# DrizzlingBytes.net
KiCad netlist of a schematic drawn in EAGLE
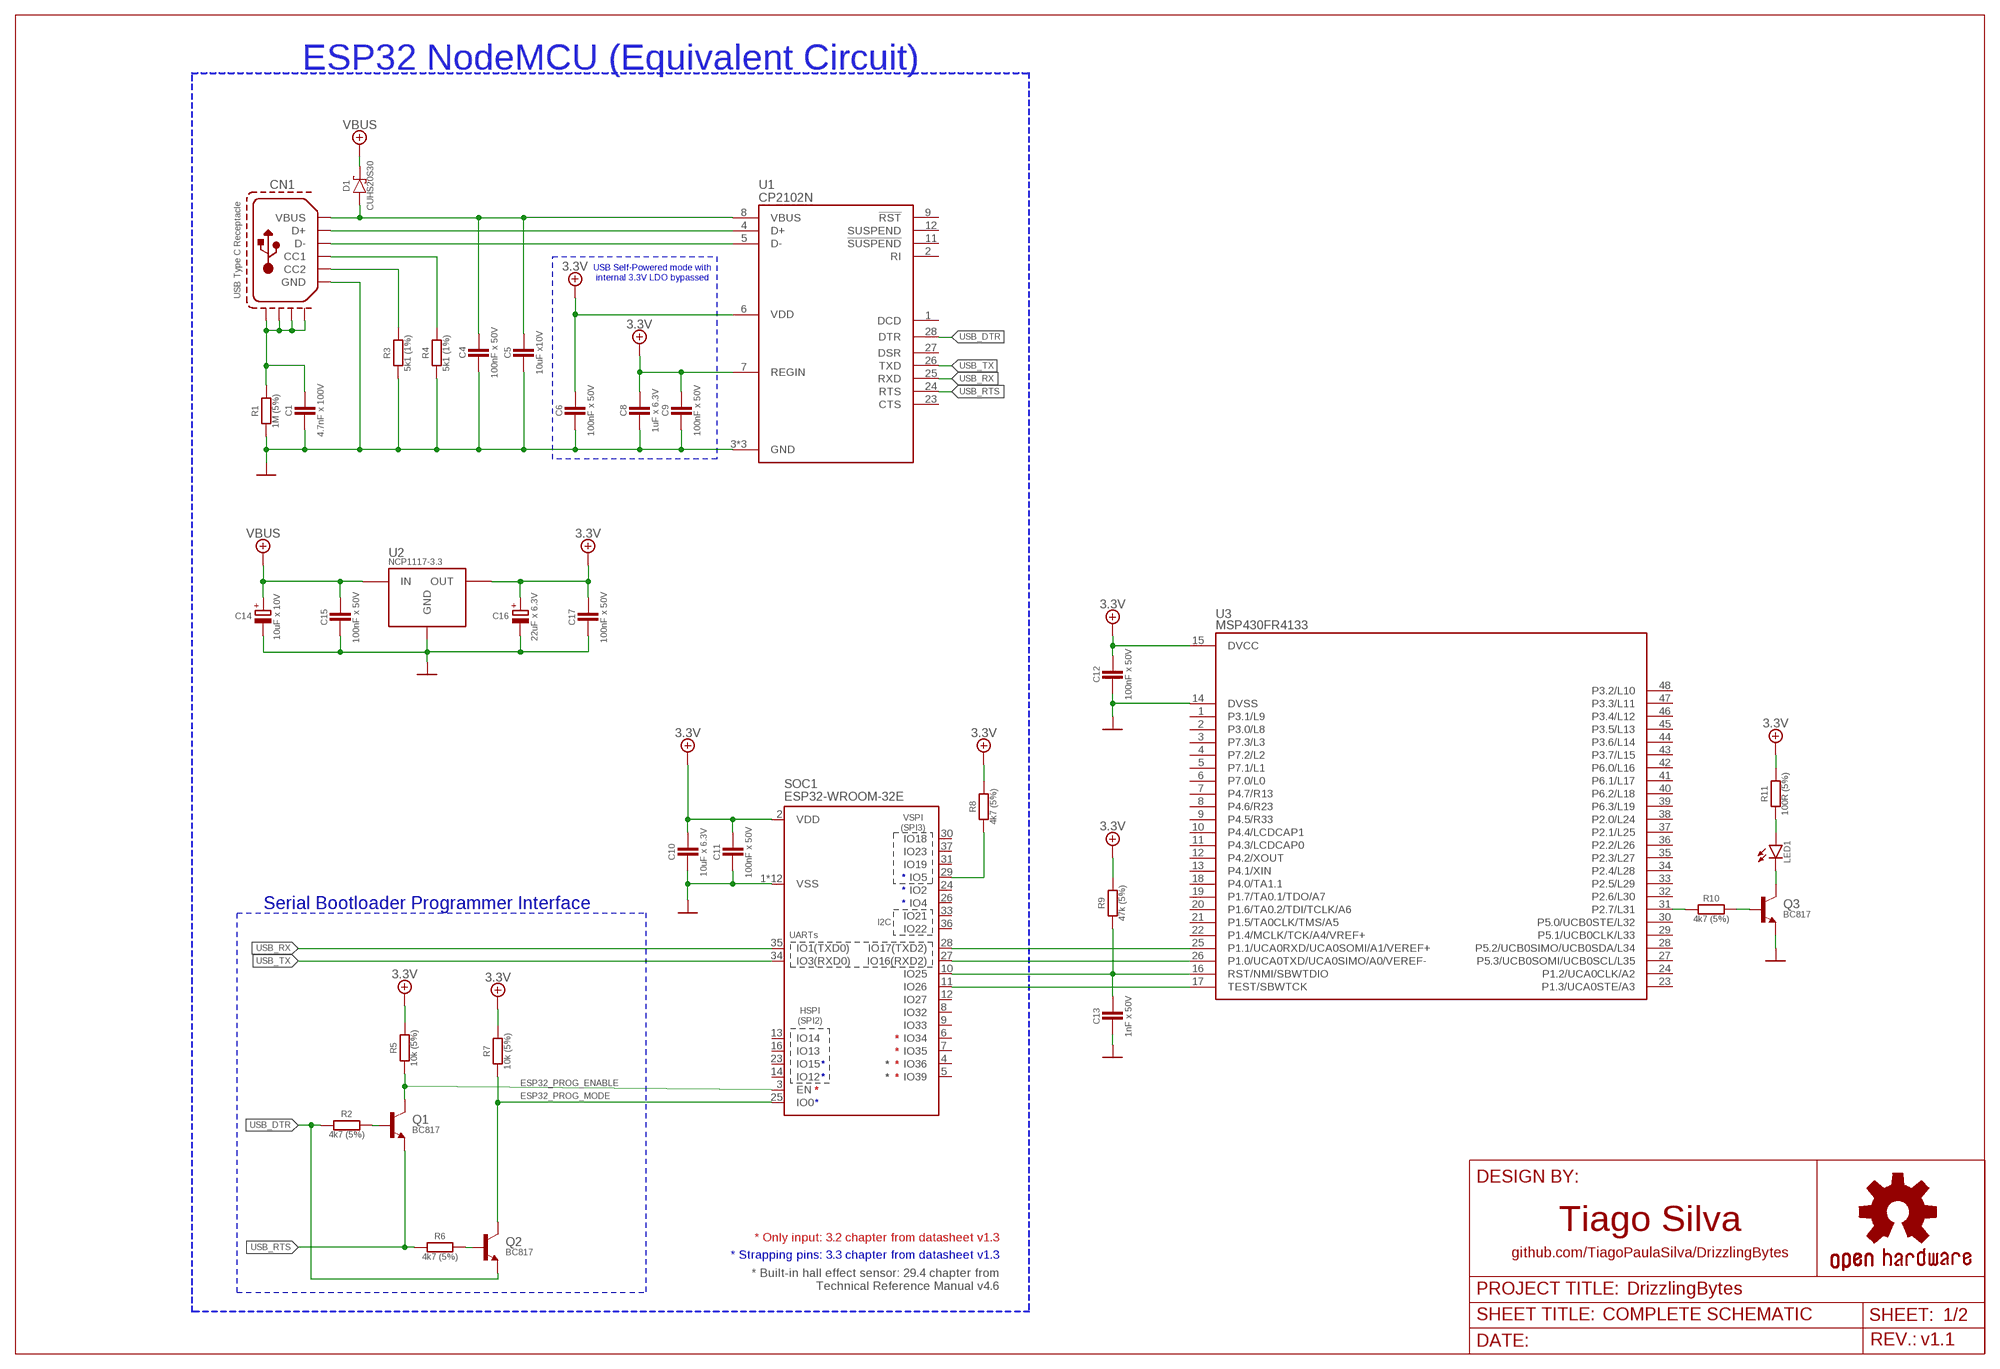
[diagram p0: schematic, sheet 1]
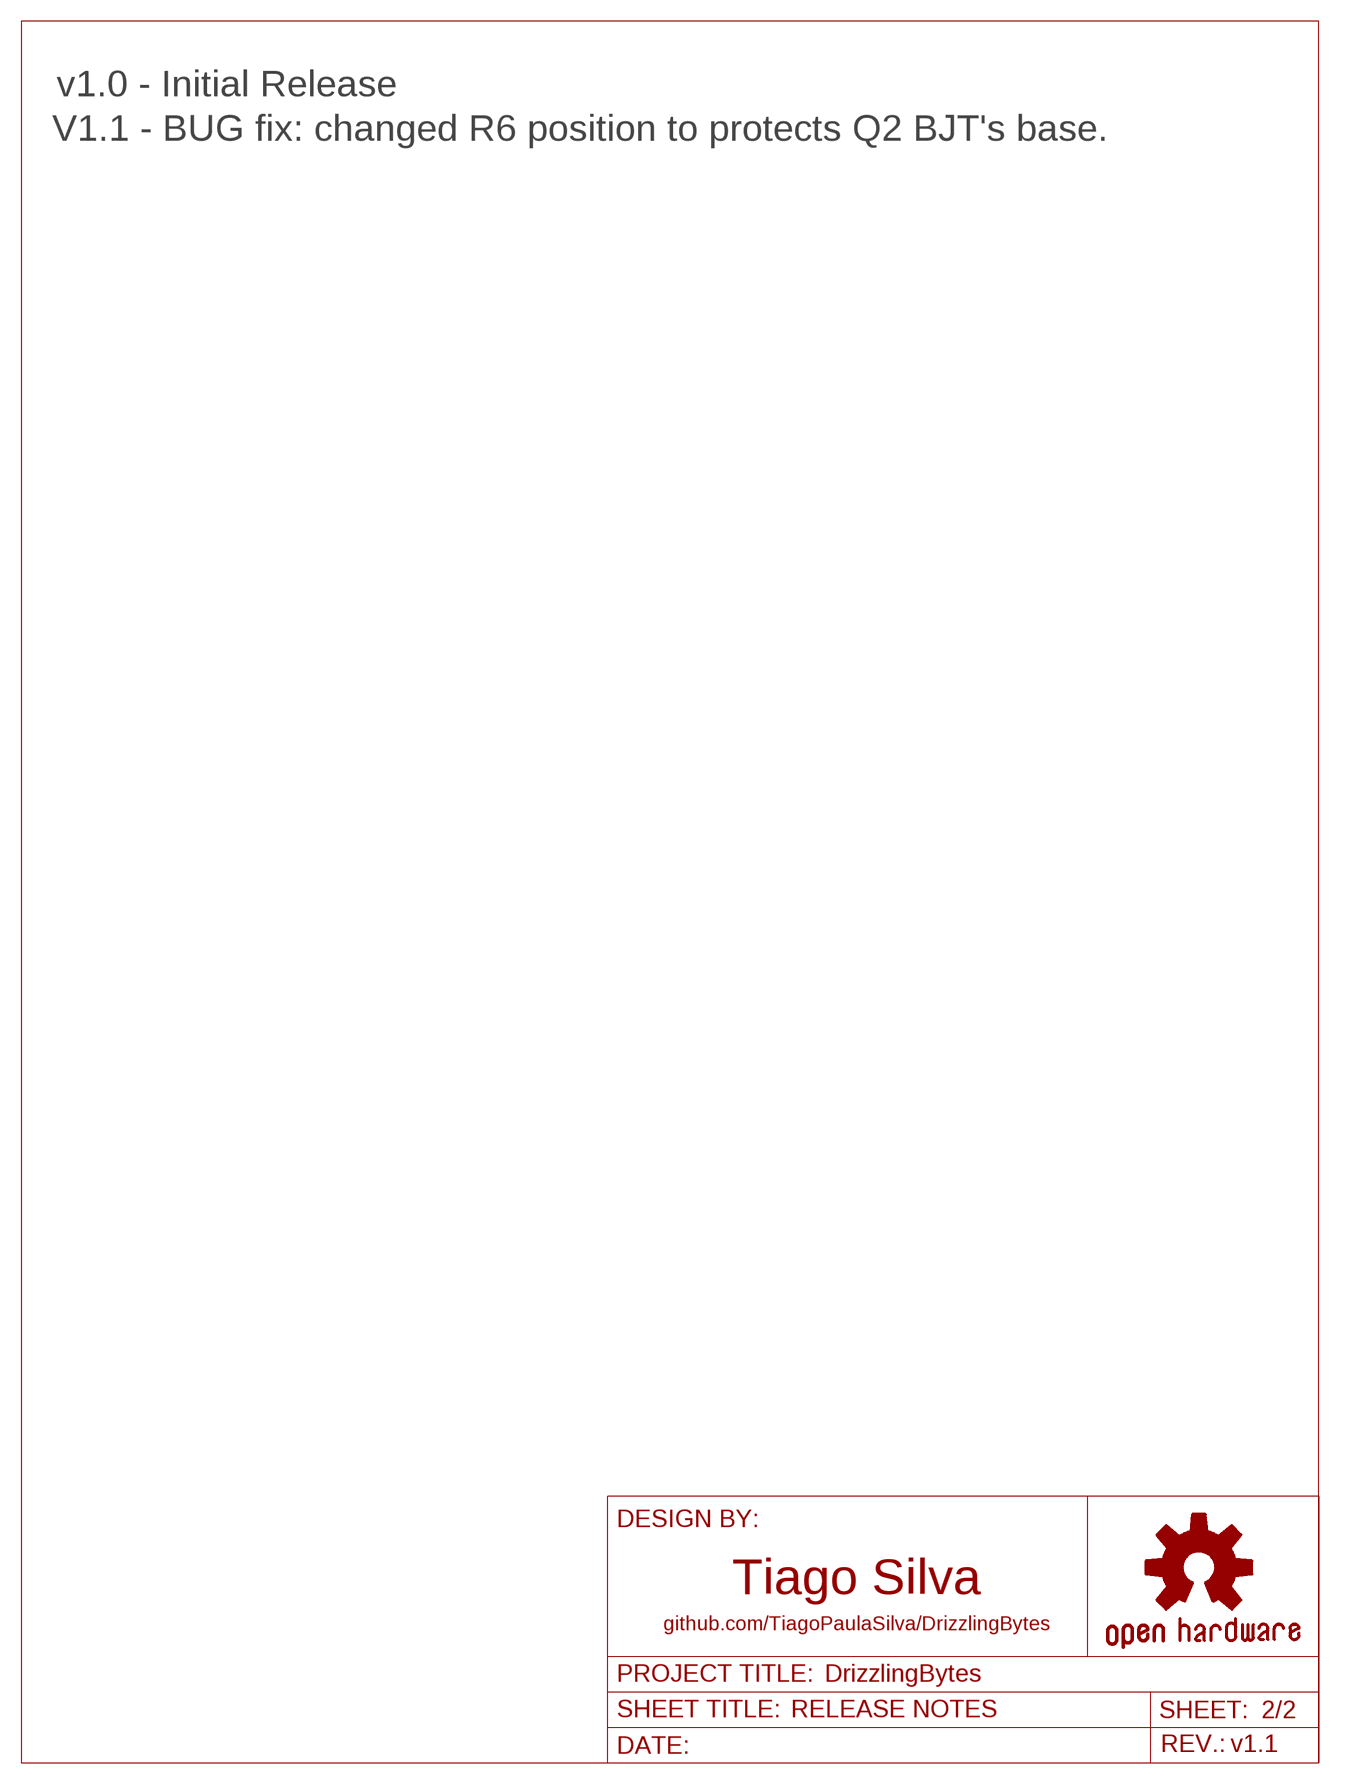
[diagram p1: schematic, sheet 2]

(export (version "E")
  (design (tool "Eeschema 10.0.6"))
  (components
    (comp (ref "C1")
      (value "4.7nF x 100V")
      (footprint "eagle-import:C0402")
      (libsource (lib "eagle-import") (part "C_0402"))
    )
    (comp (ref "C4")
      (value "100nF x 50V")
      (footprint "eagle-import:C0402")
      (libsource (lib "eagle-import") (part "C_0402"))
    )
    (comp (ref "C5")
      (value "10uF x10V")
      (footprint "eagle-import:C0402")
      (libsource (lib "eagle-import") (part "C_0402"))
    )
    (comp (ref "C6")
      (value "100nF x 50V")
      (footprint "eagle-import:C0402")
      (libsource (lib "eagle-import") (part "C_0402"))
    )
    (comp (ref "C8")
      (value "1uF x 6.3V")
      (footprint "eagle-import:C0402")
      (libsource (lib "eagle-import") (part "C_0402"))
    )
    (comp (ref "C9")
      (value "100nF x 50V")
      (footprint "eagle-import:C0402")
      (libsource (lib "eagle-import") (part "C_0402"))
    )
    (comp (ref "C10")
      (value "10uF x 6.3V")
      (footprint "eagle-import:C0402")
      (libsource (lib "eagle-import") (part "C_0402"))
    )
    (comp (ref "C11")
      (value "100nF x 50V")
      (footprint "eagle-import:C0402")
      (libsource (lib "eagle-import") (part "C_0402"))
    )
    (comp (ref "C12")
      (value "100nF x 50V")
      (footprint "eagle-import:C0402")
      (libsource (lib "eagle-import") (part "C_0402"))
    )
    (comp (ref "C13")
      (value "1nF x 50V")
      (footprint "eagle-import:C0402")
      (libsource (lib "eagle-import") (part "C_0402"))
    )
    (comp (ref "C14")
      (value "10uF x 10V")
      (footprint "eagle-import:C1206_POL")
      (description "Tantalum Electrolytic Capacitors (Low ESR)")
      (libsource (lib "eagle-import") (part "CP_1206_POL"))
    )
    (comp (ref "C15")
      (value "100nF x 50V")
      (footprint "eagle-import:C0402")
      (libsource (lib "eagle-import") (part "C_0402"))
    )
    (comp (ref "C16")
      (value "22uF x 6.3V")
      (footprint "eagle-import:C1206_POL")
      (description "Tantalum Electrolytic Capacitors (Low ESR)")
      (libsource (lib "eagle-import") (part "CP_1206_POL"))
    )
    (comp (ref "C17")
      (value "100nF x 50V")
      (footprint "eagle-import:C0402")
      (libsource (lib "eagle-import") (part "C_0402"))
    )
    (comp (ref "CN1")
      (value "USB Type C Receptacle")
      (footprint "eagle-import:USB-C-16P-2LAYER-PADS")
      (libsource (lib "eagle-import") (part "USB-C-16P-2LAYERS"))
    )
    (comp (ref "D1")
      (value "SCHOTTKY-CUHS20S30")
      (footprint "eagle-import:US2H-2")
      (fields (field (name "FAMILY") "CUHS20S30"))
      (libsource (lib "eagle-import") (part "SCHOTTKY-CUHS20S30"))
    )
    (comp (ref "LED1")
      (value "LED-0402")
      (footprint "eagle-import:LED-0402")
      (libsource (lib "eagle-import") (part "LED-0402"))
    )
    (comp (ref "Q1")
      (value "NPN-BC817")
      (footprint "eagle-import:SOT23-3")
      (fields (field (name "FAMILY") "BC817"))
      (libsource (lib "eagle-import") (part "NPN-BC817"))
    )
    (comp (ref "Q2")
      (value "NPN-BC817")
      (footprint "eagle-import:SOT23-3")
      (fields (field (name "FAMILY") "BC817"))
      (libsource (lib "eagle-import") (part "NPN-BC817"))
    )
    (comp (ref "Q3")
      (value "NPN-BC817")
      (footprint "eagle-import:SOT23-3")
      (fields (field (name "FAMILY") "BC817"))
      (libsource (lib "eagle-import") (part "NPN-BC817"))
    )
    (comp (ref "R1")
      (value "1M (5%)")
      (footprint "eagle-import:R0402")
      (libsource (lib "eagle-import") (part "R_0402"))
    )
    (comp (ref "R2")
      (value "4k7 (5%)")
      (footprint "eagle-import:R0402")
      (libsource (lib "eagle-import") (part "R_0402"))
    )
    (comp (ref "R3")
      (value "5k1 (1%)")
      (footprint "eagle-import:R0402")
      (libsource (lib "eagle-import") (part "R_0402"))
    )
    (comp (ref "R4")
      (value "5k1 (1%)")
      (footprint "eagle-import:R0402")
      (libsource (lib "eagle-import") (part "R_0402"))
    )
    (comp (ref "R5")
      (value "10k (5%)")
      (footprint "eagle-import:R0402")
      (libsource (lib "eagle-import") (part "R_0402"))
    )
    (comp (ref "R6")
      (value "4k7 (5%)")
      (footprint "eagle-import:R0402")
      (libsource (lib "eagle-import") (part "R_0402"))
    )
    (comp (ref "R7")
      (value "10k (5%)")
      (footprint "eagle-import:R0402")
      (libsource (lib "eagle-import") (part "R_0402"))
    )
    (comp (ref "R8")
      (value "4k7 (5%)")
      (footprint "eagle-import:R0402")
      (libsource (lib "eagle-import") (part "R_0402"))
    )
    (comp (ref "R9")
      (value "47k (5%)")
      (footprint "eagle-import:R0402")
      (libsource (lib "eagle-import") (part "R_0402"))
    )
    (comp (ref "R10")
      (value "4k7 (5%)")
      (footprint "eagle-import:R0402")
      (libsource (lib "eagle-import") (part "R_0402"))
    )
    (comp (ref "R11")
      (value "100R (5%)")
      (footprint "eagle-import:R0402")
      (libsource (lib "eagle-import") (part "R_0402"))
    )
    (comp (ref "SOC1")
      (value "ESP32-WROOM-32E")
      (footprint "eagle-import:ESP32-WROOM-32E")
      (libsource (lib "eagle-import") (part "ESP32-WROOM-32E-N4"))
    )
    (comp (ref "U1")
      (value "CP2102N")
      (footprint "eagle-import:QFN-28")
      (libsource (lib "eagle-import") (part "CP2102N"))
    )
    (comp (ref "U2")
      (value "1117-3.3V")
      (footprint "eagle-import:SOT-223-3")
      (fields (field (name "FAMILY") "LT1117-3.3") (field (name "FAMILY_1") "NCP1117-3.3"))
      (libsource (lib "eagle-import") (part "1117-3.3V"))
    )
    (comp (ref "U3")
      (value "MSP430FR4133")
      (footprint "eagle-import:TSSOP-48")
      (fields
        (field (name "MANUFACTURER_PART_NUMBER") "MSP430FR4133IG48R")
        (field (name "MOUSER_PART_NUMBER") "595-MSP430R4133IG48R")
      )
      (libsource (lib "eagle-import") (part "MSP430FR4133IG48R"))
    )
  )
  (nets
    (net (code "1") (name "0V") (class "Default")
      (node (ref "C1") (pin "1") (pinfunction "1_1") (pintype "passive"))
      (node (ref "C10") (pin "2") (pinfunction "2_2") (pintype "passive"))
      (node (ref "C11") (pin "2") (pinfunction "2_2") (pintype "passive"))
      (node (ref "C12") (pin "1") (pinfunction "1_1") (pintype "passive"))
      (node (ref "C13") (pin "2") (pinfunction "2_2") (pintype "passive"))
      (node (ref "C14") (pin "2") (pinfunction "-_2") (pintype "passive"))
      (node (ref "C15") (pin "2") (pinfunction "2_2") (pintype "passive"))
      (node (ref "C16") (pin "2") (pinfunction "-_2") (pintype "passive"))
      (node (ref "C17") (pin "2") (pinfunction "2_2") (pintype "passive"))
      (node (ref "C4") (pin "1") (pinfunction "1_1") (pintype "passive"))
      (node (ref "C5") (pin "1") (pinfunction "1_1") (pintype "passive"))
      (node (ref "C6") (pin "1") (pinfunction "1_1") (pintype "passive"))
      (node (ref "C8") (pin "1") (pinfunction "1_1") (pintype "passive"))
      (node (ref "C9") (pin "1") (pinfunction "1_1") (pintype "passive"))
      (node (ref "CN1") (pin "GND") (pinfunction "GND_GND") (pintype "bidirectional"))
      (node (ref "CN1") (pin "GND2") (pinfunction "GND_GND2") (pintype "bidirectional"))
      (node (ref "Q3") (pin "2") (pinfunction "E_2") (pintype "passive"))
      (node (ref "R1") (pin "2") (pinfunction "2_2") (pintype "passive"))
      (node (ref "R3") (pin "2") (pinfunction "2_2") (pintype "passive"))
      (node (ref "R4") (pin "2") (pinfunction "2_2") (pintype "passive"))
      (node (ref "SOC1") (pin "1") (pinfunction "VSS_1") (pintype "power_in"))
      (node (ref "SOC1") (pin "15") (pinfunction "VSS_15") (pintype "power_in"))
      (node (ref "SOC1") (pin "38") (pinfunction "VSS_38") (pintype "power_in"))
      (node (ref "SOC1") (pin "E1") (pinfunction "VSS_E1") (pintype "power_in"))
      (node (ref "SOC1") (pin "E2") (pinfunction "VSS_E2") (pintype "power_in"))
      (node (ref "SOC1") (pin "E3") (pinfunction "VSS_E3") (pintype "power_in"))
      (node (ref "SOC1") (pin "E4") (pinfunction "VSS_E4") (pintype "power_in"))
      (node (ref "SOC1") (pin "E5") (pinfunction "VSS_E5") (pintype "power_in"))
      (node (ref "SOC1") (pin "E6") (pinfunction "VSS_E6") (pintype "power_in"))
      (node (ref "SOC1") (pin "E7") (pinfunction "VSS_E7") (pintype "power_in"))
      (node (ref "SOC1") (pin "E8") (pinfunction "VSS_E8") (pintype "power_in"))
      (node (ref "SOC1") (pin "E9") (pinfunction "VSS_E9") (pintype "power_in"))
      (node (ref "U1") (pin "3") (pinfunction "GND_3") (pintype "power_in"))
      (node (ref "U1") (pin "EXP") (pinfunction "GND_EXP") (pintype "power_in"))
      (node (ref "U1") (pin "M") (pinfunction "GND_M") (pintype "power_in"))
      (node (ref "U2") (pin "1") (pinfunction "GND_1") (pintype "bidirectional"))
      (node (ref "U3") (pin "14") (pinfunction "DVSS_14") (pintype "bidirectional"))
    )
    (net (code "2") (name "3.3V") (class "Default")
      (node (ref "C10") (pin "1") (pinfunction "1_1") (pintype "passive"))
      (node (ref "C11") (pin "1") (pinfunction "1_1") (pintype "passive"))
      (node (ref "C12") (pin "2") (pinfunction "2_2") (pintype "passive"))
      (node (ref "C16") (pin "1") (pinfunction "+_1") (pintype "passive"))
      (node (ref "C17") (pin "1") (pinfunction "1_1") (pintype "passive"))
      (node (ref "C6") (pin "2") (pinfunction "2_2") (pintype "passive"))
      (node (ref "C8") (pin "2") (pinfunction "2_2") (pintype "passive"))
      (node (ref "C9") (pin "2") (pinfunction "2_2") (pintype "passive"))
      (node (ref "R11") (pin "2") (pinfunction "2_2") (pintype "passive"))
      (node (ref "R5") (pin "1") (pinfunction "1_1") (pintype "passive"))
      (node (ref "R7") (pin "1") (pinfunction "1_1") (pintype "passive"))
      (node (ref "R8") (pin "2") (pinfunction "2_2") (pintype "passive"))
      (node (ref "R9") (pin "2") (pinfunction "2_2") (pintype "passive"))
      (node (ref "SOC1") (pin "2") (pinfunction "VDD_2") (pintype "power_in"))
      (node (ref "U1") (pin "6") (pinfunction "VDD_6") (pintype "power_in"))
      (node (ref "U1") (pin "7") (pinfunction "REGIN_7") (pintype "passive"))
      (node (ref "U2") (pin "2") (pinfunction "OUT_2") (pintype "bidirectional"))
      (node (ref "U2") (pin "4") (pinfunction "OUT_4") (pintype "bidirectional"))
      (node (ref "U3") (pin "15") (pinfunction "DVCC_15") (pintype "bidirectional"))
    )
    (net (code "3") (name "ESP32_PROG_ENABLE") (class "Default")
      (node (ref "Q1") (pin "3") (pinfunction "C_3") (pintype "passive"))
      (node (ref "R5") (pin "2") (pinfunction "2_2") (pintype "passive"))
      (node (ref "SOC1") (pin "3") (pinfunction "EN_3") (pintype "input"))
    )
    (net (code "4") (name "ESP32_PROG_MODE") (class "Default")
      (node (ref "Q2") (pin "3") (pinfunction "C_3") (pintype "passive"))
      (node (ref "R7") (pin "2") (pinfunction "2_2") (pintype "passive"))
      (node (ref "SOC1") (pin "25") (pinfunction "IO0_25") (pintype "bidirectional"))
    )
    (net (code "5") (name "Net-(CN1-CC1)") (class "Default")
      (node (ref "CN1") (pin "A5") (pinfunction "CC1_A5") (pintype "bidirectional"))
      (node (ref "R4") (pin "1") (pinfunction "1_1") (pintype "passive"))
    )
    (net (code "6") (name "Net-(CN1-CC2)") (class "Default")
      (node (ref "CN1") (pin "B5") (pinfunction "CC2_B5") (pintype "bidirectional"))
      (node (ref "R3") (pin "1") (pinfunction "1_1") (pintype "passive"))
    )
    (net (code "7") (name "Net-(CN1-S1)") (class "Default")
      (node (ref "C1") (pin "2") (pinfunction "2_2") (pintype "passive"))
      (node (ref "CN1") (pin "SHLD1") (pinfunction "S1_SHLD1") (pintype "passive"))
      (node (ref "CN1") (pin "SHLD2") (pinfunction "S2_SHLD2") (pintype "passive"))
      (node (ref "CN1") (pin "SHLD3") (pinfunction "S3_SHLD3") (pintype "passive"))
      (node (ref "CN1") (pin "SHLD4") (pinfunction "S4_SHLD4") (pintype "passive"))
      (node (ref "R1") (pin "1") (pinfunction "1_1") (pintype "passive"))
    )
    (net (code "8") (name "Net-(D1-A)") (class "Default")
      (node (ref "C4") (pin "2") (pinfunction "2_2") (pintype "passive"))
      (node (ref "C5") (pin "2") (pinfunction "2_2") (pintype "passive"))
      (node (ref "CN1") (pin "VBUS1") (pinfunction "VBUS_VBUS1") (pintype "bidirectional"))
      (node (ref "CN1") (pin "VBUS2") (pinfunction "VBUS_VBUS2") (pintype "bidirectional"))
      (node (ref "D1") (pin "2") (pinfunction "A_2") (pintype "passive"))
      (node (ref "U1") (pin "8") (pinfunction "VBUS_8") (pintype "passive"))
    )
    (net (code "9") (name "Net-(LED1-A)") (class "Default")
      (node (ref "LED1") (pin "2") (pinfunction "A_2") (pintype "passive"))
      (node (ref "R11") (pin "1") (pinfunction "1_1") (pintype "passive"))
    )
    (net (code "10") (name "Net-(LED1-K)") (class "Default")
      (node (ref "LED1") (pin "1") (pinfunction "K_1") (pintype "passive"))
      (node (ref "Q3") (pin "3") (pinfunction "C_3") (pintype "passive"))
    )
    (net (code "11") (name "Net-(Q1-B)") (class "Default")
      (node (ref "Q1") (pin "1") (pinfunction "B_1") (pintype "passive"))
      (node (ref "R2") (pin "1") (pinfunction "1_1") (pintype "passive"))
    )
    (net (code "12") (name "Net-(Q2-B)") (class "Default")
      (node (ref "Q2") (pin "1") (pinfunction "B_1") (pintype "passive"))
      (node (ref "R6") (pin "2") (pinfunction "2_2") (pintype "passive"))
    )
    (net (code "13") (name "Net-(Q3-B)") (class "Default")
      (node (ref "Q3") (pin "1") (pinfunction "B_1") (pintype "passive"))
      (node (ref "R10") (pin "2") (pinfunction "2_2") (pintype "passive"))
    )
    (net (code "14") (name "Net-(SOC1-IO5)") (class "Default")
      (node (ref "R8") (pin "1") (pinfunction "1_1") (pintype "passive"))
      (node (ref "SOC1") (pin "29") (pinfunction "IO5_29") (pintype "bidirectional"))
    )
    (net (code "15") (name "Net-(SOC1-IO16(RXD2))") (class "Default")
      (node (ref "SOC1") (pin "27") (pinfunction "IO16(RXD2)_27") (pintype "bidirectional"))
      (node (ref "U3") (pin "26") (pinfunction "P1.0/UCA0TXD/UCA0SIMO/A0/VEREF-_26") (pintype "bidirectional"))
    )
    (net (code "16") (name "Net-(SOC1-IO17(TXD2))") (class "Default")
      (node (ref "SOC1") (pin "28") (pinfunction "IO17(TXD2)_28") (pintype "bidirectional"))
      (node (ref "U3") (pin "25") (pinfunction "P1.1/UCA0RXD/UCA0SOMI/A1/VEREF+_25") (pintype "bidirectional"))
    )
    (net (code "17") (name "Net-(SOC1-IO25)") (class "Default")
      (node (ref "C13") (pin "1") (pinfunction "1_1") (pintype "passive"))
      (node (ref "R9") (pin "1") (pinfunction "1_1") (pintype "passive"))
      (node (ref "SOC1") (pin "10") (pinfunction "IO25_10") (pintype "bidirectional"))
      (node (ref "U3") (pin "16") (pinfunction "RST/NMI/SBWTDIO_16") (pintype "bidirectional"))
    )
    (net (code "18") (name "Net-(SOC1-IO26)") (class "Default")
      (node (ref "SOC1") (pin "11") (pinfunction "IO26_11") (pintype "bidirectional"))
      (node (ref "U3") (pin "17") (pinfunction "TEST/SBWTCK_17") (pintype "bidirectional"))
    )
    (net (code "19") (name "Net-(U1-D+)") (class "Default")
      (node (ref "CN1") (pin "A6") (pinfunction "D+_A6") (pintype "bidirectional"))
      (node (ref "CN1") (pin "B6") (pinfunction "D+_B6") (pintype "bidirectional"))
      (node (ref "U1") (pin "4") (pinfunction "D+_4") (pintype "bidirectional"))
    )
    (net (code "20") (name "Net-(U1-D-)") (class "Default")
      (node (ref "CN1") (pin "A7") (pinfunction "D-_A7") (pintype "bidirectional"))
      (node (ref "CN1") (pin "B7") (pinfunction "D-_B7") (pintype "bidirectional"))
      (node (ref "U1") (pin "5") (pinfunction "D-_5") (pintype "bidirectional"))
    )
    (net (code "21") (name "Net-(U3-P2.7{slash}L31)") (class "Default")
      (node (ref "R10") (pin "1") (pinfunction "1_1") (pintype "passive"))
      (node (ref "U3") (pin "31") (pinfunction "P2.7/L31_31") (pintype "bidirectional"))
    )
    (net (code "22") (name "USB_DTR") (class "Default")
      (node (ref "Q2") (pin "2") (pinfunction "E_2") (pintype "passive"))
      (node (ref "R2") (pin "2") (pinfunction "2_2") (pintype "passive"))
      (node (ref "U1") (pin "28") (pinfunction "DTR_28") (pintype "output"))
    )
    (net (code "23") (name "USB_RTS") (class "Default")
      (node (ref "Q1") (pin "2") (pinfunction "E_2") (pintype "passive"))
      (node (ref "R6") (pin "1") (pinfunction "1_1") (pintype "passive"))
      (node (ref "U1") (pin "24") (pinfunction "RTS_24") (pintype "output"))
    )
    (net (code "24") (name "USB_RX") (class "Default")
      (node (ref "SOC1") (pin "35") (pinfunction "IO1(TXD0)_35") (pintype "bidirectional"))
      (node (ref "U1") (pin "25") (pinfunction "RXD_25") (pintype "input"))
    )
    (net (code "25") (name "USB_TX") (class "Default")
      (node (ref "SOC1") (pin "34") (pinfunction "IO3(RXD0)_34") (pintype "bidirectional"))
      (node (ref "U1") (pin "26") (pinfunction "TXD_26") (pintype "output"))
    )
    (net (code "26") (name "VBUS") (class "Default")
      (node (ref "C14") (pin "1") (pinfunction "+_1") (pintype "passive"))
      (node (ref "C15") (pin "1") (pinfunction "1_1") (pintype "passive"))
      (node (ref "D1") (pin "1") (pinfunction "K_1") (pintype "passive"))
      (node (ref "U2") (pin "3") (pinfunction "IN_3") (pintype "bidirectional"))
    )
    (net (code "27") (name "unconnected-(SOC1-IO2-Pad24)") (class "Default")
      (node (ref "SOC1") (pin "24") (pinfunction "IO2_24") (pintype "bidirectional"))
    )
    (net (code "28") (name "unconnected-(SOC1-IO4-Pad26)") (class "Default")
      (node (ref "SOC1") (pin "26") (pinfunction "IO4_26") (pintype "bidirectional"))
    )
    (net (code "29") (name "unconnected-(SOC1-IO12-Pad14)") (class "Default")
      (node (ref "SOC1") (pin "14") (pinfunction "IO12_14") (pintype "bidirectional"))
    )
    (net (code "30") (name "unconnected-(SOC1-IO13-Pad16)") (class "Default")
      (node (ref "SOC1") (pin "16") (pinfunction "IO13_16") (pintype "bidirectional"))
    )
    (net (code "31") (name "unconnected-(SOC1-IO14-Pad13)") (class "Default")
      (node (ref "SOC1") (pin "13") (pinfunction "IO14_13") (pintype "bidirectional"))
    )
    (net (code "32") (name "unconnected-(SOC1-IO15-Pad23)") (class "Default")
      (node (ref "SOC1") (pin "23") (pinfunction "IO15_23") (pintype "bidirectional"))
    )
    (net (code "33") (name "unconnected-(SOC1-IO18-Pad30)") (class "Default")
      (node (ref "SOC1") (pin "30") (pinfunction "IO18_30") (pintype "bidirectional"))
    )
    (net (code "34") (name "unconnected-(SOC1-IO19-Pad31)") (class "Default")
      (node (ref "SOC1") (pin "31") (pinfunction "IO19_31") (pintype "bidirectional"))
    )
    (net (code "35") (name "unconnected-(SOC1-IO21-Pad33)") (class "Default")
      (node (ref "SOC1") (pin "33") (pinfunction "IO21_33") (pintype "bidirectional"))
    )
    (net (code "36") (name "unconnected-(SOC1-IO22-Pad36)") (class "Default")
      (node (ref "SOC1") (pin "36") (pinfunction "IO22_36") (pintype "bidirectional"))
    )
    (net (code "37") (name "unconnected-(SOC1-IO23-Pad37)") (class "Default")
      (node (ref "SOC1") (pin "37") (pinfunction "IO23_37") (pintype "bidirectional"))
    )
    (net (code "38") (name "unconnected-(SOC1-IO27-Pad12)") (class "Default")
      (node (ref "SOC1") (pin "12") (pinfunction "IO27_12") (pintype "bidirectional"))
    )
    (net (code "39") (name "unconnected-(SOC1-IO32-Pad8)") (class "Default")
      (node (ref "SOC1") (pin "8") (pinfunction "IO32_8") (pintype "bidirectional"))
    )
    (net (code "40") (name "unconnected-(SOC1-IO33-Pad9)") (class "Default")
      (node (ref "SOC1") (pin "9") (pinfunction "IO33_9") (pintype "bidirectional"))
    )
    (net (code "41") (name "unconnected-(SOC1-IO34-Pad6)") (class "Default")
      (node (ref "SOC1") (pin "6") (pinfunction "IO34_6") (pintype "bidirectional"))
    )
    (net (code "42") (name "unconnected-(SOC1-IO35-Pad7)") (class "Default")
      (node (ref "SOC1") (pin "7") (pinfunction "IO35_7") (pintype "bidirectional"))
    )
    (net (code "43") (name "unconnected-(SOC1-IO36-Pad4)") (class "Default")
      (node (ref "SOC1") (pin "4") (pinfunction "IO36_4") (pintype "bidirectional"))
    )
    (net (code "44") (name "unconnected-(SOC1-IO39-Pad5)") (class "Default")
      (node (ref "SOC1") (pin "5") (pinfunction "IO39_5") (pintype "bidirectional"))
    )
    (net (code "45") (name "unconnected-(U1-CTS-Pad23)") (class "Default")
      (node (ref "U1") (pin "23") (pinfunction "CTS_23") (pintype "passive"))
    )
    (net (code "46") (name "unconnected-(U1-DCD-Pad1)") (class "Default")
      (node (ref "U1") (pin "1") (pinfunction "DCD_1") (pintype "passive"))
    )
    (net (code "47") (name "unconnected-(U1-DSR-Pad27)") (class "Default")
      (node (ref "U1") (pin "27") (pinfunction "DSR_27") (pintype "passive"))
    )
    (net (code "48") (name "unconnected-(U1-RI-Pad2)") (class "Default")
      (node (ref "U1") (pin "2") (pinfunction "RI_2") (pintype "passive"))
    )
    (net (code "49") (name "unconnected-(U1-SUSPEND-Pad12)") (class "Default")
      (node (ref "U1") (pin "12") (pinfunction "SUSPEND_12") (pintype "passive"))
    )
    (net (code "50") (name "unconnected-(U1-~{RST}-Pad9)") (class "Default")
      (node (ref "U1") (pin "9") (pinfunction "~{RST}_9") (pintype "bidirectional"))
    )
    (net (code "51") (name "unconnected-(U1-~{SUSPEND}-Pad11)") (class "Default")
      (node (ref "U1") (pin "11") (pinfunction "~{SUSPEND}_11") (pintype "output"))
    )
    (net (code "52") (name "unconnected-(U3-P1.2{slash}UCA0CLK{slash}A2-Pad24)") (class "Default")
      (node (ref "U3") (pin "24") (pinfunction "P1.2/UCA0CLK/A2_24") (pintype "bidirectional"))
    )
    (net (code "53") (name "unconnected-(U3-P1.3{slash}UCA0STE{slash}A3-Pad23)") (class "Default")
      (node (ref "U3") (pin "23") (pinfunction "P1.3/UCA0STE/A3_23") (pintype "bidirectional"))
    )
    (net (code "54") (name "unconnected-(U3-P1.4{slash}MCLK{slash}TCK{slash}A4{slash}VREF+-Pad22)") (class "Default")
      (node (ref "U3") (pin "22") (pinfunction "P1.4/MCLK/TCK/A4/VREF+_22") (pintype "bidirectional"))
    )
    (net (code "55") (name "unconnected-(U3-P1.5{slash}TA0CLK{slash}TMS{slash}A5-Pad21)") (class "Default")
      (node (ref "U3") (pin "21") (pinfunction "P1.5/TA0CLK/TMS/A5_21") (pintype "bidirectional"))
    )
    (net (code "56") (name "unconnected-(U3-P1.6{slash}TA0.2{slash}TDI{slash}TCLK{slash}A6-Pad20)") (class "Default")
      (node (ref "U3") (pin "20") (pinfunction "P1.6/TA0.2/TDI/TCLK/A6_20") (pintype "bidirectional"))
    )
    (net (code "57") (name "unconnected-(U3-P1.7{slash}TA0.1{slash}TDO{slash}A7-Pad19)") (class "Default")
      (node (ref "U3") (pin "19") (pinfunction "P1.7/TA0.1/TDO/A7_19") (pintype "bidirectional"))
    )
    (net (code "58") (name "unconnected-(U3-P2.0{slash}L24-Pad38)") (class "Default")
      (node (ref "U3") (pin "38") (pinfunction "P2.0/L24_38") (pintype "bidirectional"))
    )
    (net (code "59") (name "unconnected-(U3-P2.1{slash}L25-Pad37)") (class "Default")
      (node (ref "U3") (pin "37") (pinfunction "P2.1/L25_37") (pintype "bidirectional"))
    )
    (net (code "60") (name "unconnected-(U3-P2.2{slash}L26-Pad36)") (class "Default")
      (node (ref "U3") (pin "36") (pinfunction "P2.2/L26_36") (pintype "bidirectional"))
    )
    (net (code "61") (name "unconnected-(U3-P2.3{slash}L27-Pad35)") (class "Default")
      (node (ref "U3") (pin "35") (pinfunction "P2.3/L27_35") (pintype "bidirectional"))
    )
    (net (code "62") (name "unconnected-(U3-P2.4{slash}L28-Pad34)") (class "Default")
      (node (ref "U3") (pin "34") (pinfunction "P2.4/L28_34") (pintype "bidirectional"))
    )
    (net (code "63") (name "unconnected-(U3-P2.5{slash}L29-Pad33)") (class "Default")
      (node (ref "U3") (pin "33") (pinfunction "P2.5/L29_33") (pintype "bidirectional"))
    )
    (net (code "64") (name "unconnected-(U3-P2.6{slash}L30-Pad32)") (class "Default")
      (node (ref "U3") (pin "32") (pinfunction "P2.6/L30_32") (pintype "bidirectional"))
    )
    (net (code "65") (name "unconnected-(U3-P3.0{slash}L8-Pad2)") (class "Default")
      (node (ref "U3") (pin "2") (pinfunction "P3.0/L8_2") (pintype "bidirectional"))
    )
    (net (code "66") (name "unconnected-(U3-P3.1{slash}L9-Pad1)") (class "Default")
      (node (ref "U3") (pin "1") (pinfunction "P3.1/L9_1") (pintype "bidirectional"))
    )
    (net (code "67") (name "unconnected-(U3-P3.2{slash}L10-Pad48)") (class "Default")
      (node (ref "U3") (pin "48") (pinfunction "P3.2/L10_48") (pintype "bidirectional"))
    )
    (net (code "68") (name "unconnected-(U3-P3.3{slash}L11-Pad47)") (class "Default")
      (node (ref "U3") (pin "47") (pinfunction "P3.3/L11_47") (pintype "bidirectional"))
    )
    (net (code "69") (name "unconnected-(U3-P3.4{slash}L12-Pad46)") (class "Default")
      (node (ref "U3") (pin "46") (pinfunction "P3.4/L12_46") (pintype "bidirectional"))
    )
    (net (code "70") (name "unconnected-(U3-P3.5{slash}L13-Pad45)") (class "Default")
      (node (ref "U3") (pin "45") (pinfunction "P3.5/L13_45") (pintype "bidirectional"))
    )
    (net (code "71") (name "unconnected-(U3-P3.6{slash}L14-Pad44)") (class "Default")
      (node (ref "U3") (pin "44") (pinfunction "P3.6/L14_44") (pintype "bidirectional"))
    )
    (net (code "72") (name "unconnected-(U3-P3.7{slash}L15-Pad43)") (class "Default")
      (node (ref "U3") (pin "43") (pinfunction "P3.7/L15_43") (pintype "bidirectional"))
    )
    (net (code "73") (name "unconnected-(U3-P4.0{slash}TA1.1-Pad18)") (class "Default")
      (node (ref "U3") (pin "18") (pinfunction "P4.0/TA1.1_18") (pintype "bidirectional"))
    )
    (net (code "74") (name "unconnected-(U3-P4.1{slash}XIN-Pad13)") (class "Default")
      (node (ref "U3") (pin "13") (pinfunction "P4.1/XIN_13") (pintype "bidirectional"))
    )
    (net (code "75") (name "unconnected-(U3-P4.2{slash}XOUT-Pad12)") (class "Default")
      (node (ref "U3") (pin "12") (pinfunction "P4.2/XOUT_12") (pintype "bidirectional"))
    )
    (net (code "76") (name "unconnected-(U3-P4.3{slash}LCDCAP0-Pad11)") (class "Default")
      (node (ref "U3") (pin "11") (pinfunction "P4.3/LCDCAP0_11") (pintype "bidirectional"))
    )
    (net (code "77") (name "unconnected-(U3-P4.4{slash}LCDCAP1-Pad10)") (class "Default")
      (node (ref "U3") (pin "10") (pinfunction "P4.4/LCDCAP1_10") (pintype "bidirectional"))
    )
    (net (code "78") (name "unconnected-(U3-P4.5{slash}R33-Pad9)") (class "Default")
      (node (ref "U3") (pin "9") (pinfunction "P4.5/R33_9") (pintype "bidirectional"))
    )
    (net (code "79") (name "unconnected-(U3-P4.6{slash}R23-Pad8)") (class "Default")
      (node (ref "U3") (pin "8") (pinfunction "P4.6/R23_8") (pintype "bidirectional"))
    )
    (net (code "80") (name "unconnected-(U3-P4.7{slash}R13-Pad7)") (class "Default")
      (node (ref "U3") (pin "7") (pinfunction "P4.7/R13_7") (pintype "bidirectional"))
    )
    (net (code "81") (name "unconnected-(U3-P5.0{slash}UCB0STE{slash}L32-Pad30)") (class "Default")
      (node (ref "U3") (pin "30") (pinfunction "P5.0/UCB0STE/L32_30") (pintype "bidirectional"))
    )
    (net (code "82") (name "unconnected-(U3-P5.1{slash}UCB0CLK{slash}L33-Pad29)") (class "Default")
      (node (ref "U3") (pin "29") (pinfunction "P5.1/UCB0CLK/L33_29") (pintype "bidirectional"))
    )
    (net (code "83") (name "unconnected-(U3-P5.2{slash}UCB0SIMO{slash}UCB0SDA{slash}L34-Pad28)") (class "Default")
      (node (ref "U3") (pin "28") (pinfunction "P5.2/UCB0SIMO/UCB0SDA/L34_28") (pintype "bidirectional"))
    )
    (net (code "84") (name "unconnected-(U3-P5.3{slash}UCB0SOMI{slash}UCB0SCL{slash}L35-Pad27)") (class "Default")
      (node (ref "U3") (pin "27") (pinfunction "P5.3/UCB0SOMI/UCB0SCL/L35_27") (pintype "bidirectional"))
    )
    (net (code "85") (name "unconnected-(U3-P6.0{slash}L16-Pad42)") (class "Default")
      (node (ref "U3") (pin "42") (pinfunction "P6.0/L16_42") (pintype "bidirectional"))
    )
    (net (code "86") (name "unconnected-(U3-P6.1{slash}L17-Pad41)") (class "Default")
      (node (ref "U3") (pin "41") (pinfunction "P6.1/L17_41") (pintype "bidirectional"))
    )
    (net (code "87") (name "unconnected-(U3-P6.2{slash}L18-Pad40)") (class "Default")
      (node (ref "U3") (pin "40") (pinfunction "P6.2/L18_40") (pintype "bidirectional"))
    )
    (net (code "88") (name "unconnected-(U3-P6.3{slash}L19-Pad39)") (class "Default")
      (node (ref "U3") (pin "39") (pinfunction "P6.3/L19_39") (pintype "bidirectional"))
    )
    (net (code "89") (name "unconnected-(U3-P7.0{slash}L0-Pad6)") (class "Default")
      (node (ref "U3") (pin "6") (pinfunction "P7.0/L0_6") (pintype "bidirectional"))
    )
    (net (code "90") (name "unconnected-(U3-P7.1{slash}L1-Pad5)") (class "Default")
      (node (ref "U3") (pin "5") (pinfunction "P7.1/L1_5") (pintype "bidirectional"))
    )
    (net (code "91") (name "unconnected-(U3-P7.2{slash}L2-Pad4)") (class "Default")
      (node (ref "U3") (pin "4") (pinfunction "P7.2/L2_4") (pintype "bidirectional"))
    )
    (net (code "92") (name "unconnected-(U3-P7.3{slash}L3-Pad3)") (class "Default")
      (node (ref "U3") (pin "3") (pinfunction "P7.3/L3_3") (pintype "bidirectional"))
    )
  )
)
